# Schematic.net
KiCad netlist of a schematic drawn in Altium Designer
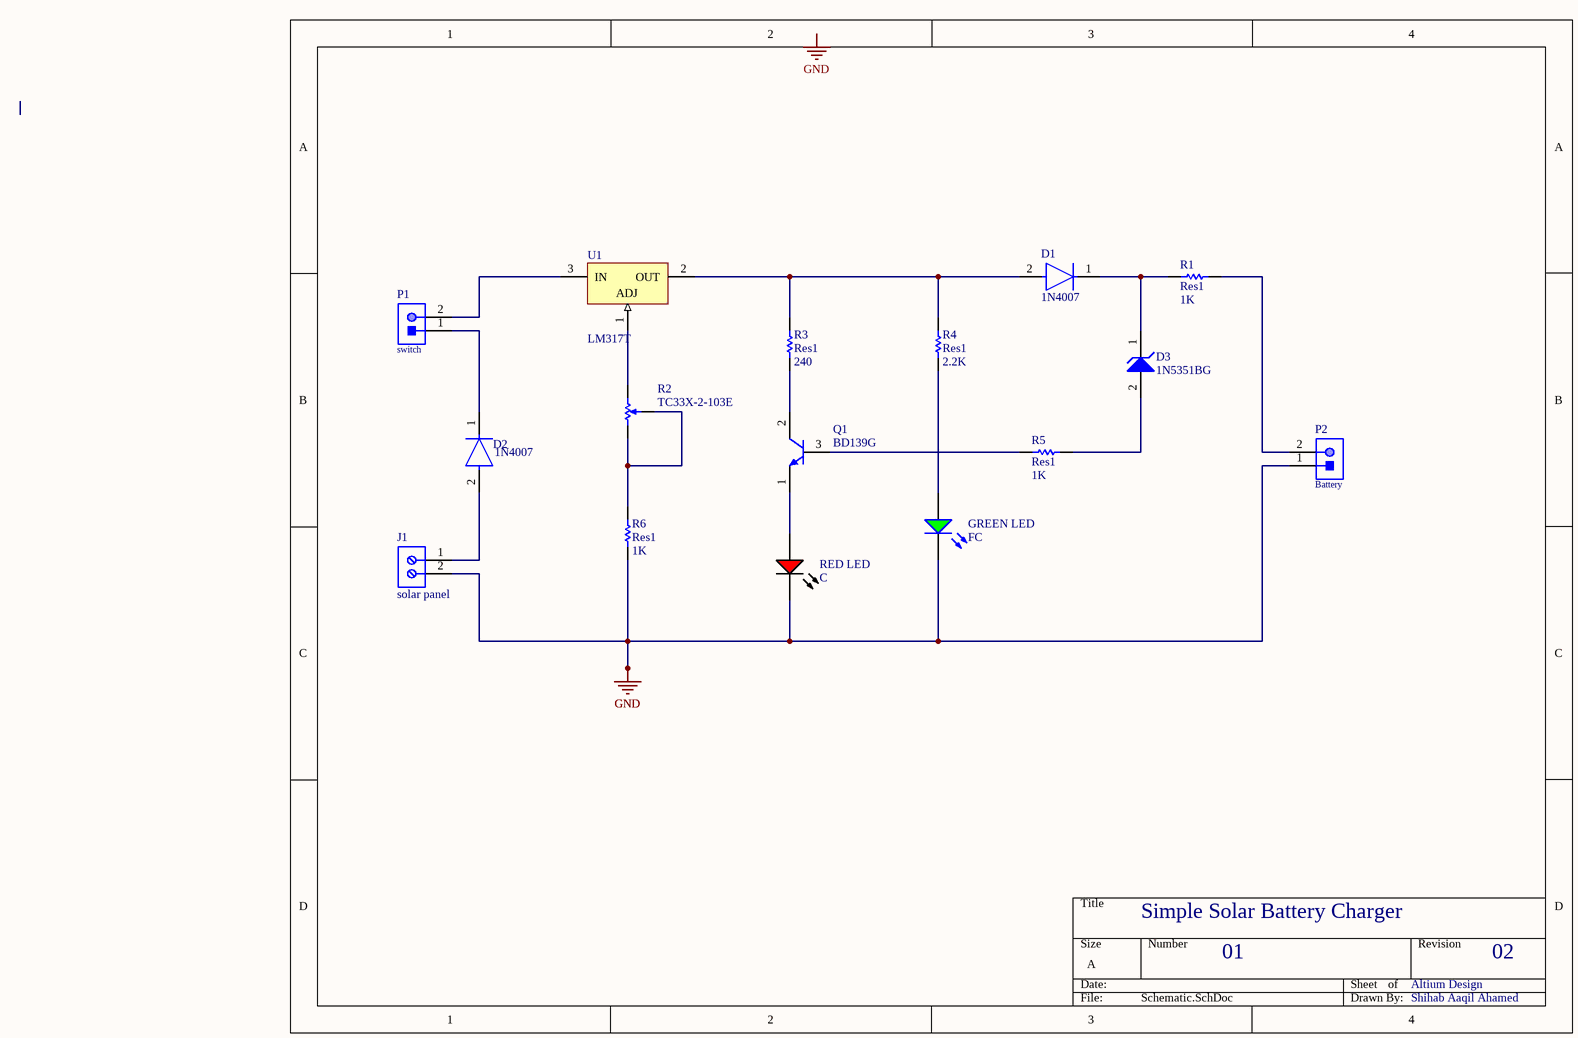
[diagram p0: Schematic.SchDoc]

(export (version "E")
  (design (tool "Eeschema 10.0.6"))
  (components
    (comp (ref "D1")
      (value "1N4007")
      (footprint "FP-1N4007-MFG")
      (description "Rectifier diode 1000 V 1 A DO-41, ,")
      (fields
        (field (name "MANUFACTURER") "Diotec")
        (field (name "OCTOPART") "https://octopart.com/1n4007-diotec-4040411")
      )
      (libsource (lib "Altium Content Vault") (part "d7152d700b627762746794eb795d46e"))
    )
    (comp (ref "D2")
      (value "1N4007")
      (footprint "FP-1N4007-MFG")
      (description "Rectifier diode 1000 V 1 A DO-41, ,")
      (fields
        (field (name "MANUFACTURER") "Diotec")
        (field (name "OCTOPART") "https://octopart.com/1n4007-diotec-4040411")
      )
      (libsource (lib "Altium Content Vault") (part "d7152d700b627762746794eb795d46e"))
    )
    (comp (ref "D3")
      (value "1N5351BG")
      (footprint "ONSC-SURMETIC40-2-017AA-01")
      (description "5 W Zener Voltage Regulator, 2-Pin Surmetic(TM) 40, Pb-Free, Bulk Box")
      (fields (field (name "MANUFACTURER") "On Semiconductor"))
      (libsource (lib "Altium Content Vault") (part "ONSC-K1A2-2"))
    )
    (comp (ref "GREEN LED")
      (value "FC")
      (footprint "AVAG-HLMP-4740")
      (description "T-1 3/4 (5 mm) Low Current LED Lamp, Green, 1.9 V, -20 to 100 degC, 2-Pin THD, RoHS, Bulk")
      (fields (field (name "MANUFACTURER") "AvagoTechnologies"))
      (libsource (lib "Altium Content Vault") (part "LED-GREEN-AK-2"))
    )
    (comp (ref "J1")
      (value "solar panel")
      (footprint "691102710002")
      (description "Series 102 - 5.00 mm Horizontal Entry Modular with Pressure Clamp WR-TBL, 2 pin")
      (fields
        (field (name "MANUFACTURER") "Wurth Elektronik")
        (field (name "PART NUMBER") "691102710002")
        (field (name "PUBLISHER") "WurthElektronik")
      )
      (libsource (lib "Altium Content Vault") (part "WE-CN-1P-F-TB2"))
    )
    (comp (ref "P1")
      (value "switch")
      (footprint "61300211121")
      (description "THT Vertical Pin Header WR-PHD, Pitch 2.54 mm, Single Row, 2 pins")
      (fields
        (field (name "MANUFACTURER") "Wurth Elektronik")
        (field (name "PART NUMBER") "61300211121")
        (field (name "PUBLISHER") "WurthElektronik")
      )
      (libsource (lib "Altium Content Vault") (part "WE-CN-1P-M-R2"))
    )
    (comp (ref "P2")
      (value "Battery")
      (footprint "61300211121")
      (description "THT Vertical Pin Header WR-PHD, Pitch 2.54 mm, Single Row, 2 pins")
      (fields
        (field (name "MANUFACTURER") "Wurth Elektronik")
        (field (name "PART NUMBER") "61300211121")
        (field (name "PUBLISHER") "WurthElektronik")
      )
      (libsource (lib "") (part "WE-CN-1P-M-R2_1"))
    )
    (comp (ref "Q1")
      (value "BD139G")
      (footprint "ONSC-TO-225-3-77-09")
      (description "Plastic Medium-Power Silicon NPN Transistor, 3-Pin TO-225, Pb-Free, Bulk Box")
      (fields (field (name "MANUFACTURER") "On Semiconductor"))
      (libsource (lib "Altium Content Vault") (part "ONSC-NPN-E1C2B3-3"))
    )
    (comp (ref "R1")
      (value "Res1")
      (footprint "AXIAL-0.3")
      (description "Resistor")
      (fields (field (name "ALTIUM_VALUE") "1K") (field (name "PUBLISHER") "Altium Limited"))
      (libsource (lib "Miscellaneous Devices") (part "Res1"))
    )
    (comp (ref "R2")
      (value "TC33X-2-103E")
      (footprint "BOUR-TC33X-2_V")
      (description "Trimming Potentiometer, 10000 Ohm, -40 to 100 degC, 3-Pin SMD, RoHS, Tape and Reel")
      (fields (field (name "TOLERANCE") "25%") (field (name "MANUFACTURER") "Bourns"))
      (libsource (lib "Altium Content Vault") (part "RES-ADJ-3_A"))
    )
    (comp (ref "R3")
      (value "Res1")
      (footprint "AXIAL-0.3")
      (description "Resistor")
      (fields (field (name "ALTIUM_VALUE") "240") (field (name "PUBLISHER") "Altium Limited"))
      (libsource (lib "Miscellaneous Devices") (part "Res1"))
    )
    (comp (ref "R4")
      (value "Res1")
      (footprint "AXIAL-0.3")
      (description "Resistor")
      (fields (field (name "ALTIUM_VALUE") "2.2K") (field (name "PUBLISHER") "Altium Limited"))
      (libsource (lib "Miscellaneous Devices") (part "Res1"))
    )
    (comp (ref "R5")
      (value "Res1")
      (footprint "AXIAL-0.3")
      (description "Resistor")
      (fields (field (name "ALTIUM_VALUE") "1K") (field (name "PUBLISHER") "Altium Limited"))
      (libsource (lib "Miscellaneous Devices") (part "Res1"))
    )
    (comp (ref "R6")
      (value "Res1")
      (footprint "AXIAL-0.3")
      (description "Resistor")
      (fields (field (name "ALTIUM_VALUE") "1K") (field (name "PUBLISHER") "Altium Limited"))
      (libsource (lib "Miscellaneous Devices") (part "Res1"))
    )
    (comp (ref "RED LED")
      (value "C")
      (footprint "AVAG-HLMP-3301-2")
      (description "T-1 3/4 (5 mm) Diffused LED Lamp, 1.9 V, -40 to 100 degC, 2-Pin THD, RoHS, Bulk")
      (fields (field (name "MANUFACTURER") "Avago"))
      (libsource (lib "Altium Content Vault") (part "LED-RED-K1A2-2"))
    )
    (comp (ref "U1")
      (value "LM317T")
      (footprint "TO-220")
      (description "1.5A, 1.2V to 37V Adjustable Voltage Regulator, 3-Pin TO-220")
      (libsource (lib "Altium Content Vault") (part "PM-REG-117-SIL3"))
    )
  )
  (nets
    (net (code "1") (name "GND") (class "Default")
      (node (ref "GREEN LED") (pin "2") (pinfunction "K_2") (pintype "passive"))
      (node (ref "J1") (pin "2") (pinfunction "2_2") (pintype "passive"))
      (node (ref "P2") (pin "1") (pinfunction "1_1") (pintype "passive"))
      (node (ref "R6") (pin "1") (pinfunction "1_1") (pintype "passive"))
      (node (ref "RED LED") (pin "1") (pinfunction "K_1") (pintype "passive"))
    )
    (net (code "2") (name "Net-(D1-A)") (class "Default")
      (node (ref "D1") (pin "2") (pinfunction "A_2") (pintype "passive"))
      (node (ref "R3") (pin "2") (pinfunction "2_2") (pintype "passive"))
      (node (ref "R4") (pin "2") (pinfunction "2_2") (pintype "passive"))
      (node (ref "U1") (pin "2") (pinfunction "OUT_2") (pintype "power_in"))
    )
    (net (code "3") (name "Net-(D1-C)") (class "Default")
      (node (ref "D1") (pin "1") (pinfunction "C_1") (pintype "passive"))
      (node (ref "D3") (pin "1") (pinfunction "K_1") (pintype "passive"))
      (node (ref "R1") (pin "1") (pinfunction "1_1") (pintype "passive"))
    )
    (net (code "4") (name "Net-(D2-A)") (class "Default")
      (node (ref "D2") (pin "2") (pinfunction "A_2") (pintype "passive"))
      (node (ref "J1") (pin "1") (pinfunction "1_1") (pintype "passive"))
    )
    (net (code "5") (name "Net-(D2-C)") (class "Default")
      (node (ref "D2") (pin "1") (pinfunction "C_1") (pintype "passive"))
      (node (ref "P1") (pin "1") (pinfunction "1_1") (pintype "passive"))
    )
    (net (code "6") (name "Net-(D3-A)") (class "Default")
      (node (ref "D3") (pin "2") (pinfunction "A_2") (pintype "passive"))
      (node (ref "R5") (pin "2") (pinfunction "2_2") (pintype "passive"))
    )
    (net (code "7") (name "Net-(GREEN LED-A)") (class "Default")
      (node (ref "GREEN LED") (pin "1") (pinfunction "A_1") (pintype "passive"))
      (node (ref "R4") (pin "1") (pinfunction "1_1") (pintype "passive"))
    )
    (net (code "8") (name "Net-(P2-Pad2)") (class "Default")
      (node (ref "P2") (pin "2") (pinfunction "2_2") (pintype "passive"))
      (node (ref "R1") (pin "2") (pinfunction "2_2") (pintype "passive"))
    )
    (net (code "9") (name "Net-(Q1-B)") (class "Default")
      (node (ref "Q1") (pin "3") (pinfunction "B_3") (pintype "passive"))
      (node (ref "R5") (pin "1") (pinfunction "1_1") (pintype "passive"))
    )
    (net (code "10") (name "Net-(Q1-C)") (class "Default")
      (node (ref "Q1") (pin "2") (pinfunction "C_2") (pintype "passive"))
      (node (ref "R3") (pin "1") (pinfunction "1_1") (pintype "passive"))
    )
    (net (code "11") (name "Net-(Q1-E)") (class "Default")
      (node (ref "Q1") (pin "1") (pinfunction "E_1") (pintype "passive"))
      (node (ref "RED LED") (pin "2") (pinfunction "A_2") (pintype "passive"))
    )
    (net (code "12") (name "Net-(R2-Pad1)") (class "Default")
      (node (ref "R2") (pin "1") (pinfunction "1_1") (pintype "passive"))
      (node (ref "R2") (pin "2") (pinfunction "2_2") (pintype "passive"))
      (node (ref "R6") (pin "2") (pinfunction "2_2") (pintype "passive"))
    )
    (net (code "13") (name "Net-(U1-ADJ)") (class "Default")
      (node (ref "R2") (pin "3") (pinfunction "3_3") (pintype "passive"))
      (node (ref "U1") (pin "1") (pinfunction "ADJ_1") (pintype "input"))
    )
    (net (code "14") (name "Net-(U1-IN)") (class "Default")
      (node (ref "P1") (pin "2") (pinfunction "2_2") (pintype "passive"))
      (node (ref "U1") (pin "3") (pinfunction "IN_3") (pintype "power_in"))
    )
  )
)
